# NBT_RS232_TESTPLUG.net
KiCad netlist of a schematic drawn in Altium Designer
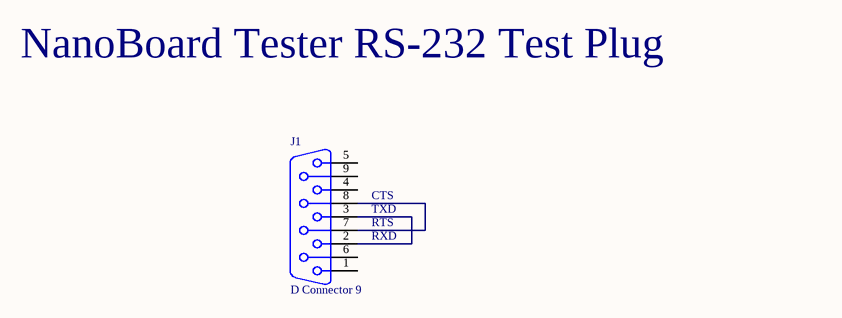
[diagram p0: NBT_RS232_TESTPLUG.SchDoc]

(export (version "E")
  (design (tool "Eeschema 10.0.6"))
  (components
    (comp (ref "J1")
      (value "D Connector 9")
      (footprint "DSUB1.385-2H9")
      (description "Receptacle Assembly, 9 Position, Right Angle")
      (fields (field (name "MANUFACTURER") "Generic Components") (field (name "PUBLISHER") "Altium Limited"))
      (libsource (lib "Miscellaneous Connectors") (part "D Connector 9"))
    )
  )
  (nets
    (net (code "1") (name "Net-(J1-Pad2)") (class "Default")
      (node (ref "J1") (pin "2") (pinfunction "2_2") (pintype "passive"))
      (node (ref "J1") (pin "3") (pinfunction "3_3") (pintype "passive"))
    )
    (net (code "2") (name "Net-(J1-Pad7)") (class "Default")
      (node (ref "J1") (pin "7") (pinfunction "7_7") (pintype "passive"))
      (node (ref "J1") (pin "8") (pinfunction "8_8") (pintype "passive"))
    )
    (net (code "3") (name "unconnected-(J1-MH1-Pad10)") (class "Default")
      (node (ref "J1") (pin "10") (pinfunction "MH1_10") (pintype "passive"))
    )
    (net (code "4") (name "unconnected-(J1-MH2-Pad11)") (class "Default")
      (node (ref "J1") (pin "11") (pinfunction "MH2_11") (pintype "passive"))
    )
    (net (code "5") (name "unconnected-(J1-Pad1)") (class "Default")
      (node (ref "J1") (pin "1") (pinfunction "1_1") (pintype "passive"))
    )
    (net (code "6") (name "unconnected-(J1-Pad4)") (class "Default")
      (node (ref "J1") (pin "4") (pinfunction "4_4") (pintype "passive"))
    )
    (net (code "7") (name "unconnected-(J1-Pad5)") (class "Default")
      (node (ref "J1") (pin "5") (pinfunction "5_5") (pintype "passive"))
    )
    (net (code "8") (name "unconnected-(J1-Pad6)") (class "Default")
      (node (ref "J1") (pin "6") (pinfunction "6_6") (pintype "passive"))
    )
    (net (code "9") (name "unconnected-(J1-Pad9)") (class "Default")
      (node (ref "J1") (pin "9") (pinfunction "9_9") (pintype "passive"))
    )
  )
)
